# Sheet1.net
KiCad netlist of a schematic drawn in Altium Designer
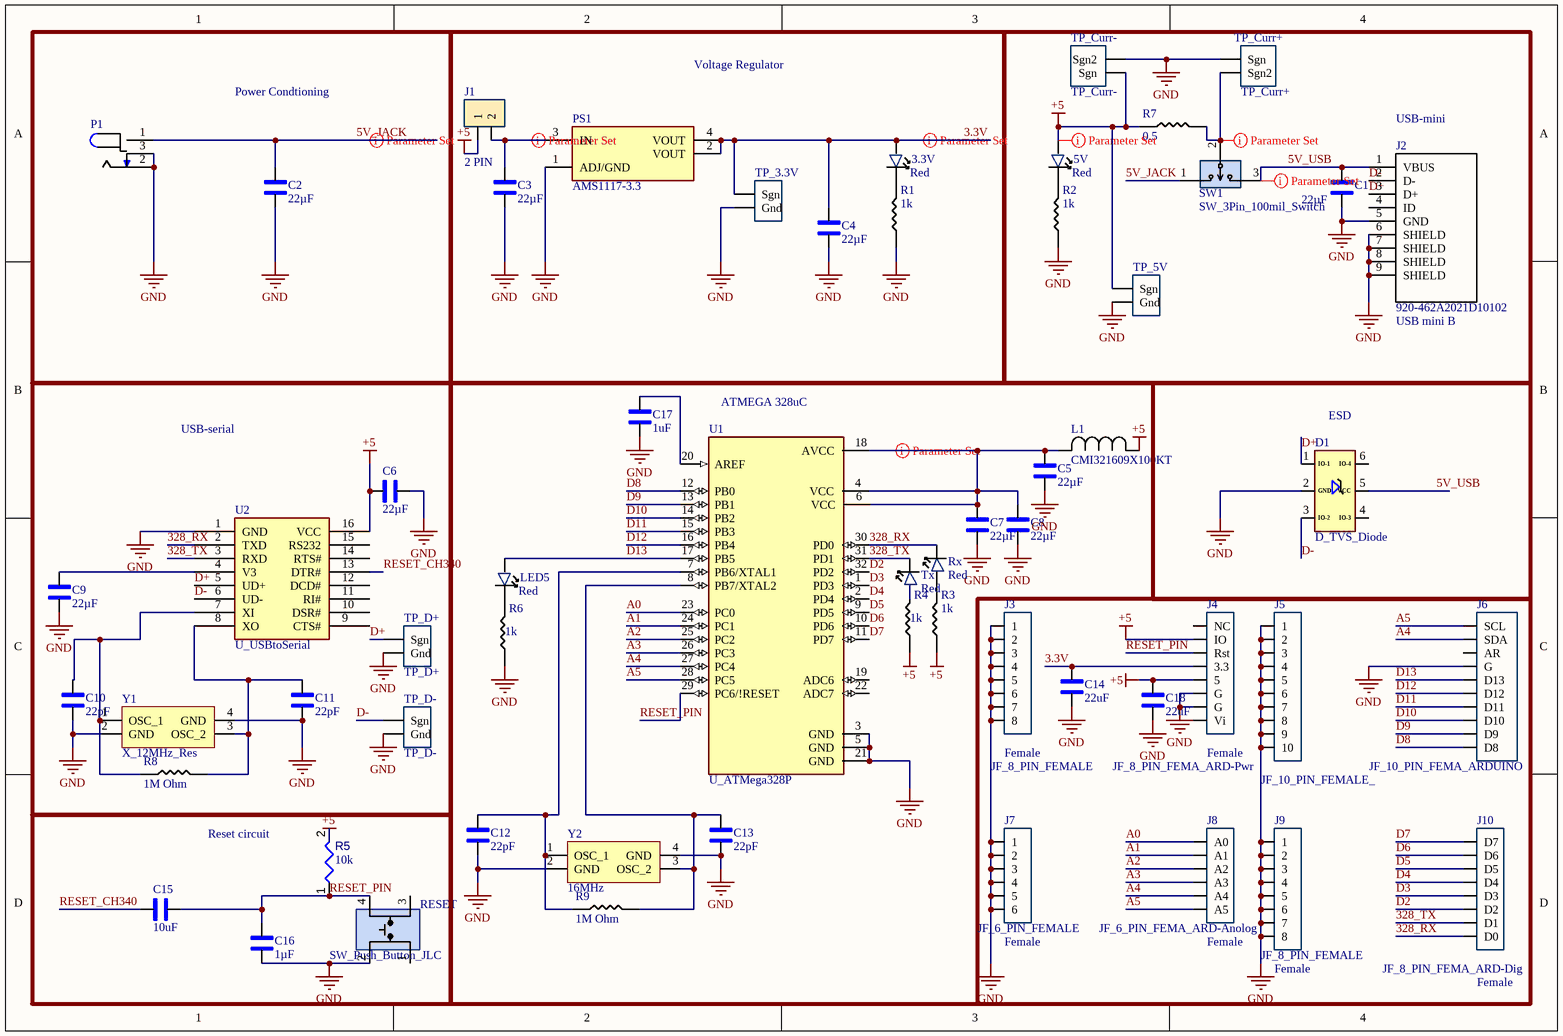
[diagram p0: Sheet1.SchDoc]

(export (version "E")
  (design (tool "Eeschema 10.0.6"))
  (components
    (comp (ref "3.3V")
      (value "Red")
      (footprint "LED_1206")
      (description "Red 621~631nm 1206 Light Emitting Diodes (LED) RoHS")
      (fields (field (name "LCSC PART#") "C93133") (field (name "MFR PART #") "15-21/R6C-FQ1R1B/2T"))
      (libsource (lib "University of Colorado") (part "LED_YELLOW_1206"))
    )
    (comp (ref "5V")
      (value "Red")
      (footprint "LED_1206")
      (description "Red 621~631nm 1206 Light Emitting Diodes (LED) RoHS")
      (fields (field (name "LCSC PART#") "C93133") (field (name "MFR PART #") "15-21/R6C-FQ1R1B/2T"))
      (libsource (lib "University of Colorado") (part "LED_YELLOW_1206"))
    )
    (comp (ref "C1")
      (value "22µF")
      (footprint "1206_Passive_Capacitor")
      (description "22uF ±10% 25V X5R 1206 Multilayer Ceramic Capacitors MLCC - SMD/SMT RoHS")
      (fields (field (name "LCSC PART#") "C12891") (field (name "MFR PART #") "CL31A226KAHNNNE"))
      (libsource (lib "University of Colorado") (part "C_47nF_1206"))
    )
    (comp (ref "C2")
      (value "22µF")
      (footprint "1206_Passive_Capacitor")
      (description "22uF ±10% 25V X5R 1206 Multilayer Ceramic Capacitors MLCC - SMD/SMT RoHS")
      (fields (field (name "LCSC PART#") "C12891") (field (name "MFR PART #") "CL31A226KAHNNNE"))
      (libsource (lib "University of Colorado") (part "C_47nF_1206"))
    )
    (comp (ref "C3")
      (value "22µF")
      (footprint "1206_Passive_Capacitor")
      (description "22uF ±10% 25V X5R 1206 Multilayer Ceramic Capacitors MLCC - SMD/SMT RoHS")
      (fields (field (name "LCSC PART#") "C12891") (field (name "MFR PART #") "CL31A226KAHNNNE"))
      (libsource (lib "University of Colorado") (part "C_47nF_1206"))
    )
    (comp (ref "C4")
      (value "22µF")
      (footprint "1206_Passive_Capacitor")
      (description "22uF ±10% 25V X5R 1206 Multilayer Ceramic Capacitors MLCC - SMD/SMT RoHS")
      (fields (field (name "LCSC PART#") "C12891") (field (name "MFR PART #") "CL31A226KAHNNNE"))
      (libsource (lib "University of Colorado") (part "C_47nF_1206"))
    )
    (comp (ref "C5")
      (value "22µF")
      (footprint "1206_Passive_Capacitor")
      (description "22uF ±10% 25V X5R 1206 Multilayer Ceramic Capacitors MLCC - SMD/SMT RoHS")
      (fields (field (name "LCSC PART#") "C12891") (field (name "MFR PART #") "CL31A226KAHNNNE"))
      (libsource (lib "University of Colorado") (part "C_47nF_1206"))
    )
    (comp (ref "C6")
      (value "22µF")
      (footprint "1206_Passive_Capacitor")
      (description "22uF ±10% 25V X5R 1206 Multilayer Ceramic Capacitors MLCC - SMD/SMT RoHS")
      (fields (field (name "LCSC PART#") "C12891") (field (name "MFR PART #") "CL31A226KAHNNNE"))
      (libsource (lib "University of Colorado") (part "C_47nF_1206"))
    )
    (comp (ref "C7")
      (value "22µF")
      (footprint "1206_Passive_Capacitor")
      (description "22uF ±10% 25V X5R 1206 Multilayer Ceramic Capacitors MLCC - SMD/SMT RoHS")
      (fields (field (name "LCSC PART#") "C12891") (field (name "MFR PART #") "CL31A226KAHNNNE"))
      (libsource (lib "University of Colorado") (part "C_47nF_1206"))
    )
    (comp (ref "C8")
      (value "22µF")
      (footprint "1206_Passive_Capacitor")
      (description "22uF ±10% 25V X5R 1206 Multilayer Ceramic Capacitors MLCC - SMD/SMT RoHS")
      (fields (field (name "LCSC PART#") "C12891") (field (name "MFR PART #") "CL31A226KAHNNNE"))
      (libsource (lib "University of Colorado") (part "C_47nF_1206"))
    )
    (comp (ref "C9")
      (value "22µF")
      (footprint "1206_Passive_Capacitor")
      (description "22uF ±10% 25V X5R 1206 Multilayer Ceramic Capacitors MLCC - SMD/SMT RoHS")
      (fields (field (name "LCSC PART#") "C12891") (field (name "MFR PART #") "CL31A226KAHNNNE"))
      (libsource (lib "University of Colorado") (part "C_47nF_1206"))
    )
    (comp (ref "C10")
      (value "22pF")
      (footprint "1206_Passive_Capacitor")
      (description "22uF ±10% 25V X5R 1206 Multilayer Ceramic Capacitors MLCC - SMD/SMT RoHS")
      (fields (field (name "LCSC PART#") "C12891") (field (name "MFR PART #") "CL31A226KAHNNNE"))
      (libsource (lib "University of Colorado") (part "C_47nF_1206"))
    )
    (comp (ref "C11")
      (value "22pF")
      (footprint "1206_Passive_Capacitor")
      (description "22uF ±10% 25V X5R 1206 Multilayer Ceramic Capacitors MLCC - SMD/SMT RoHS")
      (fields (field (name "LCSC PART#") "C12891") (field (name "MFR PART #") "CL31A226KAHNNNE"))
      (libsource (lib "University of Colorado") (part "C_47nF_1206"))
    )
    (comp (ref "C12")
      (value "22pF")
      (footprint "1206_Passive_Capacitor")
      (description "22uF ±10% 25V X5R 1206 Multilayer Ceramic Capacitors MLCC - SMD/SMT RoHS")
      (fields (field (name "LCSC PART#") "C12891") (field (name "MFR PART #") "CL31A226KAHNNNE"))
      (libsource (lib "University of Colorado") (part "C_47nF_1206"))
    )
    (comp (ref "C13")
      (value "22pF")
      (footprint "1206_Passive_Capacitor")
      (description "22uF ±10% 25V X5R 1206 Multilayer Ceramic Capacitors MLCC - SMD/SMT RoHS")
      (fields (field (name "LCSC PART#") "C12891") (field (name "MFR PART #") "CL31A226KAHNNNE"))
      (libsource (lib "University of Colorado") (part "C_47nF_1206"))
    )
    (comp (ref "C14")
      (value "22uF")
      (footprint "1206_Passive_Capacitor")
      (description "22uF ±10% 25V X5R 1206 Multilayer Ceramic Capacitors MLCC - SMD/SMT RoHS")
      (fields (field (name "MFR PART #") "CL31A226KAHNNNE") (field (name "LCSC PART#") "C12891"))
      (libsource (lib "ECEN5730Lib_2023_05_DS") (part "C_22uF_1206"))
    )
    (comp (ref "C15")
      (value "10uF")
      (footprint "1206_Passive_Capacitor")
      (description "10uF ±10% 50V X5R 1206 Multilayer Ceramic Capacitors MLCC - SMD/SMT RoHS")
      (fields (field (name "LCSC PART#") "C13585") (field (name "MFR PART #") "CL31A106KBHNNNE"))
      (libsource (lib "ECEN5730Lib_2023_05_DS") (part "C_10uF_1206"))
    )
    (comp (ref "C16")
      (value "1µF")
      (footprint "1206_Passive_Capacitor")
      (description "MULTILAYER CERAMIC CAPACITORS MLCC - SMD/SMT 1UF 50V 1206 ROHS")
      (fields (field (name "MFR PART #") "CL31B105KBHNNNE") (field (name "LCSC PART#") "C1848"))
      (libsource (lib "University of Colorado") (part "C_47nF_1206"))
    )
    (comp (ref "C17")
      (value "1uF")
      (footprint "1206_Passive_Capacitor")
      (description "MULTILAYER CERAMIC CAPACITORS MLCC - SMD/SMT 1UF 50V 1206 ROHS")
      (fields (field (name "MFR PART #") "CL31B105KBHNNNE") (field (name "LCSC PART#") "C1848"))
      (libsource (lib "ECEN5730Lib_2023_05_DS") (part "C_1uF_1206"))
    )
    (comp (ref "C18")
      (value "22uF")
      (footprint "1206_Passive_Capacitor")
      (description "22uF ±10% 25V X5R 1206 Multilayer Ceramic Capacitors MLCC - SMD/SMT RoHS")
      (fields (field (name "MFR PART #") "CL31A226KAHNNNE") (field (name "LCSC PART#") "C12891"))
      (libsource (lib "ECEN5730Lib_2023_05_DS") (part "C_22uF_1206"))
    )
    (comp (ref "D1")
      (value "D_TVS_Diode")
      (footprint "TVS")
      (description "TVS SOT-23-6 ROHS")
      (fields (field (name "LCSC PART#") "C85364") (field (name "MFR PART #") "SRV05-4-P-T7"))
      (libsource (lib "University of Colorado") (part "D_TVS_Diode"))
    )
    (comp (ref "J1")
      (value "2 PIN")
      (footprint "2_PIN_100MIL")
      (description "2.54mm Straight 2 1 Header,Breakaway Through Hole,P=2.54mm Pin Header & Female Header ROHS")
      (fields (field (name "LCSC PART#") "C124375") (field (name "MFR PART #") "B-2100S02P-A110"))
      (libsource (lib "University of Colorado") (part "JM_2_PIN_MALE"))
    )
    (comp (ref "J2")
      (value "USB mini B")
      (footprint "USB_MINI_B")
      (description "Through Hole USB Connectors RoHS")
      (fields
        (field (name "LCSC PART#") "C46398")
        (field (name "MFR PART #") "920-462A2021D10102")
        (field (name "Comment") "J_USB_B_Mini")
      )
      (libsource (lib "University of Colorado") (part "J_USB_B_Mini"))
    )
    (comp (ref "J3")
      (value "JF_8_PIN_FEMALE")
      (footprint "8_PIN_100MIL - Female")
      (description "8 Position Header Connector 0.100\" (2.54mm) Through Hole Tin")
      (fields
        (field (name "ALTIUM_VALUE") "Female")
        (field (name "MFR PART #") "PPTC081LFBN-RC")
        (field (name "LCSC PART#") "C27438")
      )
      (libsource (lib "University of Colorado") (part "JF_8_PIN_FEMALE"))
    )
    (comp (ref "J4")
      (value "JF_8_PIN_FEMA_ARD-Pwr")
      (footprint "8_PIN_ARD-PWR_100MIL")
      (description "8 Position Header Connector 0.100\" (2.54mm) Through Hole Tin")
      (fields
        (field (name "ALTIUM_VALUE") "Female")
        (field (name "LCSC PART#") "C27438")
        (field (name "MFR PART #") "PPTC081LFBN-RC")
      )
      (libsource (lib "University of Colorado") (part "JF_8_PIN_FEMA_ARD-Pwr"))
    )
    (comp (ref "J5")
      (value "JF_10_PIN_FEMALE_")
      (footprint "10_PIN_100MIL - Female")
      (description "10 Position Header Connector 0.100\" (2.54mm) Through Hole Tin")
      (fields (field (name "LCSC PART#") "C225507") (field (name "MFR PART #") "PPTC101LFBN-RC"))
      (libsource (lib "University of Colorado") (part "JF_10_PIN_FEMALE_"))
    )
    (comp (ref "J6")
      (value "JF_10_PIN_FEMA_ARDUINO")
      (footprint "10_PIN_ARDUINO_100MIL")
      (description "10 Position Header Connector 0.100\" (2.54mm) Through Hole Tin")
      (fields (field (name "LCSC PART#") "C225507") (field (name "MFR PART #") "PPTC101LFBN-RC"))
      (libsource (lib "University of Colorado") (part "JF_10_PIN_FEMA_ARDUINO"))
    )
    (comp (ref "J7")
      (value "JF_6_PIN_FEMALE")
      (footprint "6_PIN_100MIL -Female")
      (description "6 Position Header Connector 0.100\" (2.54mm) Through Hole Tin")
      (fields
        (field (name "ALTIUM_VALUE") "Female")
        (field (name "LCSC PART#") "C40877")
        (field (name "MFR PART #") "PPTC061LFBN-RC")
      )
      (libsource (lib "University of Colorado") (part "JF_6_PIN_FEMALE"))
    )
    (comp (ref "J8")
      (value "JF_6_PIN_FEMA_ARD-Anolog")
      (footprint "6_PIN_ARD-Analog_100mil")
      (description "6 Position Header Connector 0.100\" (2.54mm) Through Hole Tin")
      (fields
        (field (name "ALTIUM_VALUE") "Female")
        (field (name "LCSC PART#") "C40877")
        (field (name "MFR PART #") "PPTC061LFBN-RC")
      )
      (libsource (lib "University of Colorado") (part "JF_6_PIN_FEMA_ARD-Anolog"))
    )
    (comp (ref "J9")
      (value "JF_8_PIN_FEMALE")
      (footprint "8_PIN_100MIL - Female")
      (description "8 Position Header Connector 0.100\" (2.54mm) Through Hole Tin")
      (fields
        (field (name "ALTIUM_VALUE") "Female")
        (field (name "MFR PART #") "PPTC081LFBN-RC")
        (field (name "LCSC PART#") "C27438")
      )
      (libsource (lib "University of Colorado") (part "JF_8_PIN_FEMALE"))
    )
    (comp (ref "J10")
      (value "JF_8_PIN_FEMA_ARD-Dig")
      (footprint "8_PIN_ARD-DIG_100MIL")
      (description "8 Position Header Connector 0.100\" (2.54mm) Through Hole Tin")
      (fields
        (field (name "ALTIUM_VALUE") "Female")
        (field (name "LCSC PART#") "C27438")
        (field (name "MFR PART #") "PPTC081LFBN-RC")
      )
      (libsource (lib "University of Colorado") (part "JF_8_PIN_FEMA_ARD-Dig"))
    )
    (comp (ref "L1")
      (value "FB_10uH_1206")
      (footprint "AIML-1206_ABR-M")
      (description "25mA 10uH ±10% 800mO 1206  Inductors (SMD) ROHS")
      (fields (field (name "LCSC PART#") "C1051") (field (name "MFR PART #") "CMI321609X100KT"))
      (libsource (lib "University of Colorado") (part "FB_10uH_1206"))
    )
    (comp (ref "LED5")
      (value "Red")
      (footprint "LED_1206")
      (description "Red 621~631nm 1206 Light Emitting Diodes (LED) RoHS")
      (fields (field (name "LCSC PART#") "C93133") (field (name "MFR PART #") "15-21/R6C-FQ1R1B/2T"))
      (libsource (lib "University of Colorado") (part "LED_YELLOW_1206"))
    )
    (comp (ref "P1")
      (value "P_Power Jack")
      (footprint "Power_Jack")
      (description "Power Barrel Connector Jack 2.10mm ID (0.083\"), 5.50mm OD (0.217\") Through Hole, Right Angle")
      (fields (field (name "LCSC PART#") "C136744") (field (name "MFR PART #") "PJ-102A"))
      (libsource (lib "University of Colorado") (part "P_Power Jack"))
    )
    (comp (ref "PS1")
      (value "PS_AMS_LDO_3v3")
      (footprint "LDO")
      (description "LOW DROPOUT REGULATORS(LDO) POSITIVE FIXED 1.3V @ 800MA 15V 3.3V 1A SOT-223 ROHS")
      (fields (field (name "MFR PART #") "AMS1117-3.3") (field (name "LCSC PART#") "C6186"))
      (libsource (lib "University of Colorado") (part "PS_AMS_LDO_3v3"))
    )
    (comp (ref "R1")
      (value "1k")
      (footprint "1206_Passive_Resitor")
      (description "CHIP RESISTOR - SURFACE MOUNT 1KOHMS ±1% 1/4W 1206 ROHS")
      (fields (field (name "LCSC PART#") "C4410") (field (name "MFR PART #") "RNCP1206FTD1K00CT"))
      (libsource (lib "University of Colorado") (part "R_500mOhm_1206"))
    )
    (comp (ref "R2")
      (value "1k")
      (footprint "1206_Passive_Resitor")
      (description "CHIP RESISTOR - SURFACE MOUNT 1KOHMS ±1% 1/4W 1206 ROHS")
      (fields (field (name "LCSC PART#") "C4410") (field (name "MFR PART #") "RNCP1206FTD1K00CT"))
      (libsource (lib "University of Colorado") (part "R_500mOhm_1206"))
    )
    (comp (ref "R3")
      (value "1k")
      (footprint "1206_Passive_Resitor")
      (description "CHIP RESISTOR - SURFACE MOUNT 1KOHMS ±1% 1/4W 1206 ROHS")
      (fields (field (name "LCSC PART#") "C4410") (field (name "MFR PART #") "RNCP1206FTD1K00CT"))
      (libsource (lib "University of Colorado") (part "R_500mOhm_1206"))
    )
    (comp (ref "R4")
      (value "1k")
      (footprint "1206_Passive_Resitor")
      (description "CHIP RESISTOR - SURFACE MOUNT 1KOHMS ±1% 1/4W 1206 ROHS")
      (fields (field (name "LCSC PART#") "C4410") (field (name "MFR PART #") "RNCP1206FTD1K00CT"))
      (libsource (lib "University of Colorado") (part "R_500mOhm_1206"))
    )
    (comp (ref "R5")
      (value "10k")
      (footprint "RESC3216X60X45ML15T20")
      (description "Chip Resistor, 10 KOhm, +/- 1%, 0.25 W, -55 to 155 degC, 1206 (3216 Metric)")
      (fields (field (name "TOLERANCE") "1%") (field (name "POWER") "250mW"))
      (libsource (lib "University of Colorado") (part "RES-2"))
    )
    (comp (ref "R6")
      (value "1k")
      (footprint "1206_Passive_Resitor")
      (description "CHIP RESISTOR - SURFACE MOUNT 1KOHMS ±1% 1/4W 1206 ROHS")
      (fields (field (name "LCSC PART#") "C4410") (field (name "MFR PART #") "RNCP1206FTD1K00CT"))
      (libsource (lib "University of Colorado") (part "R_500mOhm_1206"))
    )
    (comp (ref "R7")
      (value "0.5")
      (footprint "1206_Passive_Resitor")
      (description "Resistors/Shunt 250mW 500mO ±800ppm/? ±5% 1206  Current Sense  Resistors ROHS")
      (fields (field (name "MFR PART #") "1206W4J050KT5E") (field (name "LCSC PART#") "C247433"))
      (libsource (lib "University of Colorado") (part "R_500mOhm_1206"))
    )
    (comp (ref "R8")
      (value "1M Ohm")
      (footprint "1206_Passive_Resitor")
      (description "CHIP RESISTOR - SURFACE MOUNT 1MOHMS ±1% 1/4W 1206 ROHS")
      (fields (field (name "MFR PART #") "RMCF1206JT1M00") (field (name "LCSC PART#") "C17927"))
      (libsource (lib "ECEN5730Lib_2023_05_DS") (part "R_1M_1206"))
    )
    (comp (ref "R9")
      (value "1M Ohm")
      (footprint "1206_Passive_Resitor")
      (description "CHIP RESISTOR - SURFACE MOUNT 1MOHMS ±1% 1/4W 1206 ROHS")
      (fields (field (name "MFR PART #") "RMCF1206JT1M00") (field (name "LCSC PART#") "C17927"))
      (libsource (lib "ECEN5730Lib_2023_05_DS") (part "R_1M_1206"))
    )
    (comp (ref "RESET")
      (value "SW_Push_Button_JLC")
      (footprint "Switch_JLC")
      (description "Tactile Switch SPST-NO Top Actuated Surface Mount")
      (fields (field (name "MFR PART #") "KH-4.5X4.5X4.3H-STM") (field (name "LCSC PART#") "C2837550"))
      (libsource (lib "University of Colorado") (part "SW_Push_Button_JLC"))
    )
    (comp (ref "Rx")
      (value "Red")
      (footprint "LED_1206")
      (description "Red 621~631nm 1206 Light Emitting Diodes (LED) RoHS")
      (fields (field (name "LCSC PART#") "C93133") (field (name "MFR PART #") "15-21/R6C-FQ1R1B/2T"))
      (libsource (lib "University of Colorado") (part "LED_YELLOW_1206"))
    )
    (comp (ref "SW1")
      (value "SW_3Pin_100mil_Switch")
      (footprint "3_PIN_100mil")
      (description "Connector Header Through Hole 3 position 0.100\" (2.54mm)")
      (fields (field (name "LCSC PART#") "C49257") (field (name "MFR PART #") "PREC003SAAN-RC"))
      (libsource (lib "University of Colorado") (part "SW_3Pin_100mil_Switch"))
    )
    (comp (ref "TP_3.3V")
      (value "TP_10x_Probe")
      (footprint "TP10x_Probe")
      (description "Test Point 300 mil centers")
      (libsource (lib "University of Colorado") (part "TP_10x_Probe"))
    )
    (comp (ref "TP_5V")
      (value "TP_10x_Probe")
      (footprint "TP10x_Probe")
      (description "Test Point 300 mil centers")
      (libsource (lib "University of Colorado") (part "TP_10x_Probe"))
    )
    (comp (ref "TP_Curr+")
      (value "TP_Curr+")
      (footprint "TP_Diff_Probe")
      (description "Test Point 300 mil centers")
      (libsource (lib "University of Colorado") (part "TP_Diff_Probe"))
    )
    (comp (ref "TP_Curr-")
      (value "TP_Curr-")
      (footprint "TP_Diff_Probe")
      (description "Test Point 300 mil centers")
      (libsource (lib "") (part "TP_Diff_Probe_1"))
    )
    (comp (ref "TP_D+")
      (value "TP_D+")
      (footprint "TP10x_Probe")
      (description "Test Point 300 mil centers")
      (libsource (lib "University of Colorado") (part "TP_10x_Probe"))
    )
    (comp (ref "TP_D-")
      (value "TP_D-")
      (footprint "TP10x_Probe")
      (description "Test Point 300 mil centers")
      (libsource (lib "University of Colorado") (part "TP_10x_Probe"))
    )
    (comp (ref "Tx")
      (value "Red")
      (footprint "LED_1206")
      (description "Red 621~631nm 1206 Light Emitting Diodes (LED) RoHS")
      (fields (field (name "LCSC PART#") "C93133") (field (name "MFR PART #") "15-21/R6C-FQ1R1B/2T"))
      (libsource (lib "University of Colorado") (part "LED_YELLOW_1206"))
    )
    (comp (ref "U1")
      (value "U_ATMega328P")
      (footprint "ATMega328P")
      (description "AVR AVR® ATmega Microcontroller IC 8-Bit 20MHz 32KB (16K x 16) FLASH 32-TQFP (7x7)")
      (fields (field (name "MFR PART #") "ATMEGA328P-AU") (field (name "LCSC PART#") "C14877"))
      (libsource (lib "University of Colorado") (part "U_ATMega328P"))
    )
    (comp (ref "U2")
      (value "U_USBtoSerial")
      (footprint "USB to serial")
      (description "Transceiver USB 2.0 2Mbps SOP-16_150mil USB ICs RoHS")
      (fields (field (name "LCSC PART#") "C14267") (field (name "MFR PART #") "CH340G"))
      (libsource (lib "University of Colorado") (part "U_USBtoSerial"))
    )
    (comp (ref "Y1")
      (value "X_12MHz_Res")
      (footprint "Crystal resonator")
      (description "SMD Crystal Resonators 12MHz ±10ppm SMD-3225_4P RoHS")
      (fields (field (name "MFR PART #") "X322512MSB4SI") (field (name "LCSC PART#") "C9002"))
      (libsource (lib "University of Colorado") (part "X_12MHz_Res"))
    )
    (comp (ref "Y2")
      (value "16MHz")
      (footprint "Crystal resonator")
      (description "±10ppm 16000000Hz -40℃~85℃ 贴片无源晶振 60Ω 9pF SMD3225-4P Crystals ROHS")
      (fields (field (name "LCSC PART#") "C13738") (field (name "MFR PART #") "X322516MLB4SI"))
      (libsource (lib "ECEN5730Lib_2023_05_DS") (part "X_16Mhz_Res"))
    )
  )
  (nets
    (net (code "1") (name "+5") (class "Default")
      (node (ref "5V") (pin "1") (pinfunction "1_1") (pintype "passive"))
      (node (ref "C18") (pin "2") (pinfunction "2_2") (pintype "passive"))
      (node (ref "C6") (pin "1") (pinfunction "1_1") (pintype "passive"))
      (node (ref "J1") (pin "1") (pinfunction "1_1") (pintype "passive"))
      (node (ref "J4") (pin "2") (pinfunction "IO_2") (pintype "passive"))
      (node (ref "J4") (pin "5") (pinfunction "5_5") (pintype "passive"))
      (node (ref "L1") (pin "1") (pinfunction "1_1") (pintype "passive"))
      (node (ref "R3") (pin "1") (pinfunction "1_1") (pintype "passive"))
      (node (ref "R4") (pin "1") (pinfunction "1_1") (pintype "passive"))
      (node (ref "R5") (pin "2") (pinfunction "2_2") (pintype "passive"))
      (node (ref "R7") (pin "1") (pinfunction "1_1") (pintype "passive"))
      (node (ref "TP_5V") (pin "1") (pinfunction "Sgn_1") (pintype "passive"))
      (node (ref "TP_Curr-") (pin "1") (pinfunction "Sgn_1") (pintype "passive"))
      (node (ref "U2") (pin "16") (pinfunction "VCC_16") (pintype "passive"))
    )
    (net (code "2") (name "/3.3V") (class "Default")
      (node (ref "3.3V") (pin "1") (pinfunction "1_1") (pintype "passive"))
      (node (ref "C14") (pin "2") (pinfunction "2_2") (pintype "passive"))
      (node (ref "C4") (pin "1") (pinfunction "1_1") (pintype "passive"))
      (node (ref "J4") (pin "4") (pinfunction "3.3_4") (pintype "passive"))
      (node (ref "PS1") (pin "2") (pinfunction "VOUT_2") (pintype "power_in"))
      (node (ref "PS1") (pin "4") (pinfunction "VOUT_4") (pintype "power_in"))
      (node (ref "TP_3.3V") (pin "1") (pinfunction "Sgn_1") (pintype "passive"))
    )
    (net (code "3") (name "/5V_JACK") (class "Default")
      (node (ref "C2") (pin "2") (pinfunction "2_2") (pintype "passive"))
      (node (ref "P1") (pin "1") (pinfunction "1_1") (pintype "power_in"))
      (node (ref "SW1") (pin "1") (pinfunction "1_1") (pintype "passive"))
    )
    (net (code "4") (name "/5V_USB") (class "Default")
      (node (ref "C1") (pin "2") (pinfunction "2_2") (pintype "passive"))
      (node (ref "D1") (pin "5") (pinfunction "VCC_5") (pintype "passive"))
      (node (ref "J2") (pin "1") (pinfunction "VBUS_1") (pintype "passive"))
      (node (ref "SW1") (pin "3") (pinfunction "3_3") (pintype "passive"))
    )
    (net (code "5") (name "/328_RX") (class "Default")
      (node (ref "J10") (pin "8") (pinfunction "D0_8") (pintype "passive"))
      (node (ref "Rx") (pin "2") (pinfunction "2_2") (pintype "passive"))
      (node (ref "U1") (pin "30") (pinfunction "PD0_30") (pintype "bidirectional"))
      (node (ref "U2") (pin "2") (pinfunction "TXD_2") (pintype "passive"))
    )
    (net (code "6") (name "/328_TX") (class "Default")
      (node (ref "J10") (pin "7") (pinfunction "D1_7") (pintype "passive"))
      (node (ref "Tx") (pin "2") (pinfunction "2_2") (pintype "passive"))
      (node (ref "U1") (pin "31") (pinfunction "PD1_31") (pintype "bidirectional"))
      (node (ref "U2") (pin "3") (pinfunction "RXD_3") (pintype "passive"))
    )
    (net (code "7") (name "/A0") (class "Default")
      (node (ref "J8") (pin "1") (pinfunction "A0_1") (pintype "passive"))
      (node (ref "U1") (pin "23") (pinfunction "PC0_23") (pintype "bidirectional"))
    )
    (net (code "8") (name "/A1") (class "Default")
      (node (ref "J8") (pin "2") (pinfunction "A1_2") (pintype "passive"))
      (node (ref "U1") (pin "24") (pinfunction "PC1_24") (pintype "bidirectional"))
    )
    (net (code "9") (name "/A2") (class "Default")
      (node (ref "J8") (pin "3") (pinfunction "A2_3") (pintype "passive"))
      (node (ref "U1") (pin "25") (pinfunction "PC2_25") (pintype "bidirectional"))
    )
    (net (code "10") (name "/A3") (class "Default")
      (node (ref "J8") (pin "4") (pinfunction "A3_4") (pintype "passive"))
      (node (ref "U1") (pin "26") (pinfunction "PC3_26") (pintype "bidirectional"))
    )
    (net (code "11") (name "/A4") (class "Default")
      (node (ref "J6") (pin "2") (pinfunction "SDA_2") (pintype "passive"))
      (node (ref "J8") (pin "5") (pinfunction "A4_5") (pintype "passive"))
      (node (ref "U1") (pin "27") (pinfunction "PC4_27") (pintype "bidirectional"))
    )
    (net (code "12") (name "/A5") (class "Default")
      (node (ref "J6") (pin "1") (pinfunction "SCL_1") (pintype "passive"))
      (node (ref "J8") (pin "6") (pinfunction "A5_6") (pintype "passive"))
      (node (ref "U1") (pin "28") (pinfunction "PC5_28") (pintype "bidirectional"))
    )
    (net (code "13") (name "/D+") (class "Default")
      (node (ref "D1") (pin "1") (pinfunction "IO-1_1") (pintype "passive"))
      (node (ref "J2") (pin "3") (pinfunction "D+_3") (pintype "passive"))
      (node (ref "TP_D+") (pin "1") (pinfunction "Sgn_1") (pintype "passive"))
      (node (ref "U2") (pin "5") (pinfunction "UD+_5") (pintype "passive"))
    )
    (net (code "14") (name "/D-") (class "Default")
      (node (ref "D1") (pin "3") (pinfunction "IO-2_3") (pintype "passive"))
      (node (ref "J2") (pin "2") (pinfunction "D-_2") (pintype "passive"))
      (node (ref "TP_D-") (pin "1") (pinfunction "Sgn_1") (pintype "passive"))
      (node (ref "U2") (pin "6") (pinfunction "UD-_6") (pintype "passive"))
    )
    (net (code "15") (name "/D2") (class "Default")
      (node (ref "J10") (pin "6") (pinfunction "D2_6") (pintype "passive"))
      (node (ref "U1") (pin "32") (pinfunction "PD2_32") (pintype "bidirectional"))
    )
    (net (code "16") (name "/D3") (class "Default")
      (node (ref "J10") (pin "5") (pinfunction "D3_5") (pintype "passive"))
      (node (ref "U1") (pin "1") (pinfunction "PD3_1") (pintype "bidirectional"))
    )
    (net (code "17") (name "/D4") (class "Default")
      (node (ref "J10") (pin "4") (pinfunction "D4_4") (pintype "passive"))
      (node (ref "U1") (pin "2") (pinfunction "PD4_2") (pintype "bidirectional"))
    )
    (net (code "18") (name "/D5") (class "Default")
      (node (ref "J10") (pin "3") (pinfunction "D5_3") (pintype "passive"))
      (node (ref "U1") (pin "9") (pinfunction "PD5_9") (pintype "bidirectional"))
    )
    (net (code "19") (name "/D6") (class "Default")
      (node (ref "J10") (pin "2") (pinfunction "D6_2") (pintype "passive"))
      (node (ref "U1") (pin "10") (pinfunction "PD6_10") (pintype "bidirectional"))
    )
    (net (code "20") (name "/D7") (class "Default")
      (node (ref "J10") (pin "1") (pinfunction "D7_1") (pintype "passive"))
      (node (ref "U1") (pin "11") (pinfunction "PD7_11") (pintype "bidirectional"))
    )
    (net (code "21") (name "/D8") (class "Default")
      (node (ref "J6") (pin "10") (pinfunction "D8_10") (pintype "passive"))
      (node (ref "U1") (pin "12") (pinfunction "PB0_12") (pintype "bidirectional"))
    )
    (net (code "22") (name "/D9") (class "Default")
      (node (ref "J6") (pin "9") (pinfunction "D9_9") (pintype "passive"))
      (node (ref "U1") (pin "13") (pinfunction "PB1_13") (pintype "bidirectional"))
    )
    (net (code "23") (name "/D10") (class "Default")
      (node (ref "J6") (pin "8") (pinfunction "D10_8") (pintype "passive"))
      (node (ref "U1") (pin "14") (pinfunction "PB2_14") (pintype "bidirectional"))
    )
    (net (code "24") (name "/D11") (class "Default")
      (node (ref "J6") (pin "7") (pinfunction "D11_7") (pintype "passive"))
      (node (ref "U1") (pin "15") (pinfunction "PB3_15") (pintype "bidirectional"))
    )
    (net (code "25") (name "/D12") (class "Default")
      (node (ref "J6") (pin "6") (pinfunction "D12_6") (pintype "passive"))
      (node (ref "U1") (pin "16") (pinfunction "PB4_16") (pintype "bidirectional"))
    )
    (net (code "26") (name "/D13") (class "Default")
      (node (ref "J6") (pin "5") (pinfunction "D13_5") (pintype "passive"))
      (node (ref "LED5") (pin "1") (pinfunction "1_1") (pintype "passive"))
      (node (ref "U1") (pin "17") (pinfunction "PB5_17") (pintype "bidirectional"))
    )
    (net (code "27") (name "/RESET_CH340") (class "Default")
      (node (ref "C15") (pin "1") (pinfunction "1_1") (pintype "passive"))
      (node (ref "U2") (pin "13") (pinfunction "DTR#_13") (pintype "passive"))
    )
    (net (code "28") (name "/RESET_PIN") (class "Default")
      (node (ref "C15") (pin "2") (pinfunction "2_2") (pintype "passive"))
      (node (ref "C16") (pin "2") (pinfunction "2_2") (pintype "passive"))
      (node (ref "J4") (pin "3") (pinfunction "Rst_3") (pintype "passive"))
      (node (ref "R5") (pin "1") (pinfunction "1_1") (pintype "passive"))
      (node (ref "RESET") (pin "4") (pinfunction "4_4") (pintype "passive"))
      (node (ref "U1") (pin "29") (pinfunction "PC6/!RESET_29") (pintype "bidirectional"))
    )
    (net (code "29") (name "GND") (class "Default")
      (node (ref "C1") (pin "1") (pinfunction "1_1") (pintype "passive"))
      (node (ref "C10") (pin "1") (pinfunction "1_1") (pintype "passive"))
      (node (ref "C11") (pin "1") (pinfunction "1_1") (pintype "passive"))
      (node (ref "C12") (pin "1") (pinfunction "1_1") (pintype "passive"))
      (node (ref "C13") (pin "1") (pinfunction "1_1") (pintype "passive"))
      (node (ref "C14") (pin "1") (pinfunction "1_1") (pintype "passive"))
      (node (ref "C16") (pin "1") (pinfunction "1_1") (pintype "passive"))
      (node (ref "C17") (pin "2") (pinfunction "2_2") (pintype "passive"))
      (node (ref "C18") (pin "1") (pinfunction "1_1") (pintype "passive"))
      (node (ref "C2") (pin "1") (pinfunction "1_1") (pintype "passive"))
      (node (ref "C3") (pin "2") (pinfunction "2_2") (pintype "passive"))
      (node (ref "C4") (pin "2") (pinfunction "2_2") (pintype "passive"))
      (node (ref "C5") (pin "1") (pinfunction "1_1") (pintype "passive"))
      (node (ref "C6") (pin "2") (pinfunction "2_2") (pintype "passive"))
      (node (ref "C7") (pin "1") (pinfunction "1_1") (pintype "passive"))
      (node (ref "C8") (pin "1") (pinfunction "1_1") (pintype "passive"))
      (node (ref "C9") (pin "2") (pinfunction "2_2") (pintype "passive"))
      (node (ref "D1") (pin "2") (pinfunction "GND_2") (pintype "passive"))
      (node (ref "J2") (pin "5") (pinfunction "GND_5") (pintype "passive"))
      (node (ref "J2") (pin "6") (pinfunction "SHIELD_6") (pintype "passive"))
      (node (ref "J2") (pin "7") (pinfunction "SHIELD_7") (pintype "passive"))
      (node (ref "J2") (pin "8") (pinfunction "SHIELD_8") (pintype "passive"))
      (node (ref "J2") (pin "9") (pinfunction "SHIELD_9") (pintype "passive"))
      (node (ref "J3") (pin "1") (pinfunction "1_1") (pintype "passive"))
      (node (ref "J3") (pin "2") (pinfunction "2_2") (pintype "passive"))
      (node (ref "J3") (pin "3") (pinfunction "3_3") (pintype "passive"))
      (node (ref "J3") (pin "4") (pinfunction "4_4") (pintype "passive"))
      (node (ref "J3") (pin "5") (pinfunction "5_5") (pintype "passive"))
      (node (ref "J3") (pin "6") (pinfunction "6_6") (pintype "passive"))
      (node (ref "J3") (pin "7") (pinfunction "7_7") (pintype "passive"))
      (node (ref "J3") (pin "8") (pinfunction "8_8") (pintype "passive"))
      (node (ref "J4") (pin "6") (pinfunction "G_6") (pintype "passive"))
      (node (ref "J4") (pin "7") (pinfunction "G_7") (pintype "passive"))
      (node (ref "J5") (pin "1") (pinfunction "1_1") (pintype "passive"))
      (node (ref "J5") (pin "10") (pinfunction "10_10") (pintype "passive"))
      (node (ref "J5") (pin "2") (pinfunction "2_2") (pintype "passive"))
      (node (ref "J5") (pin "3") (pinfunction "3_3") (pintype "passive"))
      (node (ref "J5") (pin "4") (pinfunction "4_4") (pintype "passive"))
      (node (ref "J5") (pin "5") (pinfunction "5_5") (pintype "passive"))
      (node (ref "J5") (pin "6") (pinfunction "6_6") (pintype "passive"))
      (node (ref "J5") (pin "7") (pinfunction "7_7") (pintype "passive"))
      (node (ref "J5") (pin "8") (pinfunction "8_8") (pintype "passive"))
      (node (ref "J5") (pin "9") (pinfunction "9_9") (pintype "passive"))
      (node (ref "J6") (pin "4") (pinfunction "G_4") (pintype "passive"))
      (node (ref "J7") (pin "1") (pinfunction "1_1") (pintype "passive"))
      (node (ref "J7") (pin "2") (pinfunction "2_2") (pintype "passive"))
      (node (ref "J7") (pin "3") (pinfunction "3_3") (pintype "passive"))
      (node (ref "J7") (pin "4") (pinfunction "4_4") (pintype "passive"))
      (node (ref "J7") (pin "5") (pinfunction "5_5") (pintype "passive"))
      (node (ref "J7") (pin "6") (pinfunction "6_6") (pintype "passive"))
      (node (ref "J9") (pin "1") (pinfunction "1_1") (pintype "passive"))
      (node (ref "J9") (pin "2") (pinfunction "2_2") (pintype "passive"))
      (node (ref "J9") (pin "3") (pinfunction "3_3") (pintype "passive"))
      (node (ref "J9") (pin "4") (pinfunction "4_4") (pintype "passive"))
      (node (ref "J9") (pin "5") (pinfunction "5_5") (pintype "passive"))
      (node (ref "J9") (pin "6") (pinfunction "6_6") (pintype "passive"))
      (node (ref "J9") (pin "7") (pinfunction "7_7") (pintype "passive"))
      (node (ref "J9") (pin "8") (pinfunction "8_8") (pintype "passive"))
      (node (ref "P1") (pin "2") (pinfunction "2_2") (pintype "power_in"))
      (node (ref "P1") (pin "3") (pinfunction "3_3") (pintype "power_in"))
      (node (ref "PS1") (pin "1") (pinfunction "ADJ/GND_1") (pintype "passive"))
      (node (ref "R1") (pin "1") (pinfunction "1_1") (pintype "passive"))
      (node (ref "R2") (pin "1") (pinfunction "1_1") (pintype "passive"))
      (node (ref "R6") (pin "1") (pinfunction "1_1") (pintype "passive"))
      (node (ref "RESET") (pin "2") (pinfunction "2_2") (pintype "passive"))
      (node (ref "TP_3.3V") (pin "2") (pinfunction "Gnd_2") (pintype "passive"))
      (node (ref "TP_5V") (pin "2") (pinfunction "Gnd_2") (pintype "passive"))
      (node (ref "TP_Curr+") (pin "1") (pinfunction "Sgn_1") (pintype "passive"))
      (node (ref "TP_Curr-") (pin "2") (pinfunction "Sgn2_2") (pintype "passive"))
      (node (ref "TP_D+") (pin "2") (pinfunction "Gnd_2") (pintype "passive"))
      (node (ref "TP_D-") (pin "2") (pinfunction "Gnd_2") (pintype "passive"))
      (node (ref "U1") (pin "21") (pinfunction "GND_21") (pintype "power_in"))
      (node (ref "U1") (pin "3") (pinfunction "GND_3") (pintype "power_in"))
      (node (ref "U1") (pin "5") (pinfunction "GND_5") (pintype "power_in"))
      (node (ref "U2") (pin "1") (pinfunction "GND_1") (pintype "passive"))
      (node (ref "Y1") (pin "2") (pinfunction "GND_2") (pintype "passive"))
      (node (ref "Y1") (pin "4") (pinfunction "GND_4") (pintype "passive"))
      (node (ref "Y2") (pin "2") (pinfunction "GND_2") (pintype "passive"))
      (node (ref "Y2") (pin "4") (pinfunction "GND_4") (pintype "passive"))
    )
    (net (code "30") (name "Net-(3.3V-Pad2)") (class "Default")
      (node (ref "3.3V") (pin "2") (pinfunction "2_2") (pintype "passive"))
      (node (ref "R1") (pin "2") (pinfunction "2_2") (pintype "passive"))
    )
    (net (code "31") (name "Net-(5V-Pad2)") (class "Default")
      (node (ref "5V") (pin "2") (pinfunction "2_2") (pintype "passive"))
      (node (ref "R2") (pin "2") (pinfunction "2_2") (pintype "passive"))
    )
    (net (code "32") (name "Net-(LED5-Pad2)") (class "Default")
      (node (ref "LED5") (pin "2") (pinfunction "2_2") (pintype "passive"))
      (node (ref "R6") (pin "2") (pinfunction "2_2") (pintype "passive"))
    )
    (net (code "33") (name "Net-(PS1-IN)") (class "Default")
      (node (ref "C3") (pin "1") (pinfunction "1_1") (pintype "passive"))
      (node (ref "J1") (pin "2") (pinfunction "2_2") (pintype "passive"))
      (node (ref "PS1") (pin "3") (pinfunction "IN_3") (pintype "power_in"))
    )
    (net (code "34") (name "Net-(R3-Pad2)") (class "Default")
      (node (ref "R3") (pin "2") (pinfunction "2_2") (pintype "passive"))
      (node (ref "Rx") (pin "1") (pinfunction "1_1") (pintype "passive"))
    )
    (net (code "35") (name "Net-(R4-Pad2)") (class "Default")
      (node (ref "R4") (pin "2") (pinfunction "2_2") (pintype "passive"))
      (node (ref "Tx") (pin "1") (pinfunction "1_1") (pintype "passive"))
    )
    (net (code "36") (name "Net-(TP_Curr+-Sgn2)") (class "Default")
      (node (ref "R7") (pin "2") (pinfunction "2_2") (pintype "passive"))
      (node (ref "SW1") (pin "2") (pinfunction "2_2") (pintype "passive"))
      (node (ref "TP_Curr+") (pin "2") (pinfunction "Sgn2_2") (pintype "passive"))
    )
    (net (code "37") (name "Net-(U1-AREF)") (class "Default")
      (node (ref "C17") (pin "1") (pinfunction "1_1") (pintype "passive"))
      (node (ref "U1") (pin "20") (pinfunction "AREF_20") (pintype "input"))
    )
    (net (code "38") (name "Net-(U1-AVCC)") (class "Default")
      (node (ref "C5") (pin "2") (pinfunction "2_2") (pintype "passive"))
      (node (ref "C7") (pin "2") (pinfunction "2_2") (pintype "passive"))
      (node (ref "C8") (pin "2") (pinfunction "2_2") (pintype "passive"))
      (node (ref "L1") (pin "2") (pinfunction "2_2") (pintype "passive"))
      (node (ref "U1") (pin "18") (pinfunction "AVCC_18") (pintype "power_in"))
      (node (ref "U1") (pin "4") (pinfunction "VCC_4") (pintype "power_in"))
      (node (ref "U1") (pin "6") (pinfunction "VCC_6") (pintype "power_in"))
    )
    (net (code "39") (name "Net-(U1-PB6{slash}XTAL1)") (class "Default")
      (node (ref "C12") (pin "2") (pinfunction "2_2") (pintype "passive"))
      (node (ref "R9") (pin "1") (pinfunction "1_1") (pintype "passive"))
      (node (ref "U1") (pin "7") (pinfunction "PB6/XTAL1_7") (pintype "bidirectional"))
      (node (ref "Y2") (pin "1") (pinfunction "OSC_1_1") (pintype "passive"))
    )
    (net (code "40") (name "Net-(U1-PB7{slash}XTAL2)") (class "Default")
      (node (ref "C13") (pin "2") (pinfunction "2_2") (pintype "passive"))
      (node (ref "R9") (pin "2") (pinfunction "2_2") (pintype "passive"))
      (node (ref "U1") (pin "8") (pinfunction "PB7/XTAL2_8") (pintype "bidirectional"))
      (node (ref "Y2") (pin "3") (pinfunction "OSC_2_3") (pintype "passive"))
    )
    (net (code "41") (name "Net-(U2-V3)") (class "Default")
      (node (ref "C9") (pin "1") (pinfunction "1_1") (pintype "passive"))
      (node (ref "U2") (pin "4") (pinfunction "V3_4") (pintype "passive"))
    )
    (net (code "42") (name "Net-(U2-XI)") (class "Default")
      (node (ref "C10") (pin "2") (pinfunction "2_2") (pintype "passive"))
      (node (ref "R8") (pin "1") (pinfunction "1_1") (pintype "passive"))
      (node (ref "U2") (pin "7") (pinfunction "XI_7") (pintype "passive"))
      (node (ref "Y1") (pin "1") (pinfunction "OSC_1_1") (pintype "passive"))
    )
    (net (code "43") (name "Net-(U2-XO)") (class "Default")
      (node (ref "C11") (pin "2") (pinfunction "2_2") (pintype "passive"))
      (node (ref "R8") (pin "2") (pinfunction "2_2") (pintype "passive"))
      (node (ref "U2") (pin "8") (pinfunction "XO_8") (pintype "passive"))
      (node (ref "Y1") (pin "3") (pinfunction "OSC_2_3") (pintype "passive"))
    )
    (net (code "44") (name "unconnected-(D1-IO-3-Pad4)") (class "Default")
      (node (ref "D1") (pin "4") (pinfunction "IO-3_4") (pintype "passive"))
    )
    (net (code "45") (name "unconnected-(D1-IO-4-Pad6)") (class "Default")
      (node (ref "D1") (pin "6") (pinfunction "IO-4_6") (pintype "passive"))
    )
    (net (code "46") (name "unconnected-(J2-ID-Pad4)") (class "Default")
      (node (ref "J2") (pin "4") (pinfunction "ID_4") (pintype "passive"))
    )
    (net (code "47") (name "unconnected-(J4-NC-Pad1)") (class "Default")
      (node (ref "J4") (pin "1") (pinfunction "NC_1") (pintype "passive"))
    )
    (net (code "48") (name "unconnected-(J4-Vi-Pad8)") (class "Default")
      (node (ref "J4") (pin "8") (pinfunction "Vi_8") (pintype "passive"))
    )
    (net (code "49") (name "unconnected-(J6-AR-Pad3)") (class "Default")
      (node (ref "J6") (pin "3") (pinfunction "AR_3") (pintype "passive"))
    )
    (net (code "50") (name "unconnected-(RESET-Pad1)") (class "Default")
      (node (ref "RESET") (pin "1") (pinfunction "1_1") (pintype "passive"))
    )
    (net (code "51") (name "unconnected-(RESET-Pad3)") (class "Default")
      (node (ref "RESET") (pin "3") (pinfunction "3_3") (pintype "passive"))
    )
    (net (code "52") (name "unconnected-(U1-ADC6-Pad19)") (class "Default")
      (node (ref "U1") (pin "19") (pinfunction "ADC6_19") (pintype "bidirectional"))
    )
    (net (code "53") (name "unconnected-(U1-ADC7-Pad22)") (class "Default")
      (node (ref "U1") (pin "22") (pinfunction "ADC7_22") (pintype "bidirectional"))
    )
    (net (code "54") (name "unconnected-(U2-CTS#-Pad9)") (class "Default")
      (node (ref "U2") (pin "9") (pinfunction "CTS#_9") (pintype "passive"))
    )
    (net (code "55") (name "unconnected-(U2-DCD#-Pad12)") (class "Default")
      (node (ref "U2") (pin "12") (pinfunction "DCD#_12") (pintype "passive"))
    )
    (net (code "56") (name "unconnected-(U2-DSR#-Pad10)") (class "Default")
      (node (ref "U2") (pin "10") (pinfunction "DSR#_10") (pintype "passive"))
    )
    (net (code "57") (name "unconnected-(U2-RI#-Pad11)") (class "Default")
      (node (ref "U2") (pin "11") (pinfunction "RI#_11") (pintype "passive"))
    )
    (net (code "58") (name "unconnected-(U2-RS232-Pad15)") (class "Default")
      (node (ref "U2") (pin "15") (pinfunction "RS232_15") (pintype "passive"))
    )
    (net (code "59") (name "unconnected-(U2-RTS#-Pad14)") (class "Default")
      (node (ref "U2") (pin "14") (pinfunction "RTS#_14") (pintype "passive"))
    )
  )
)
